# DAC.net
KiCad netlist of a schematic drawn in Altium Designer
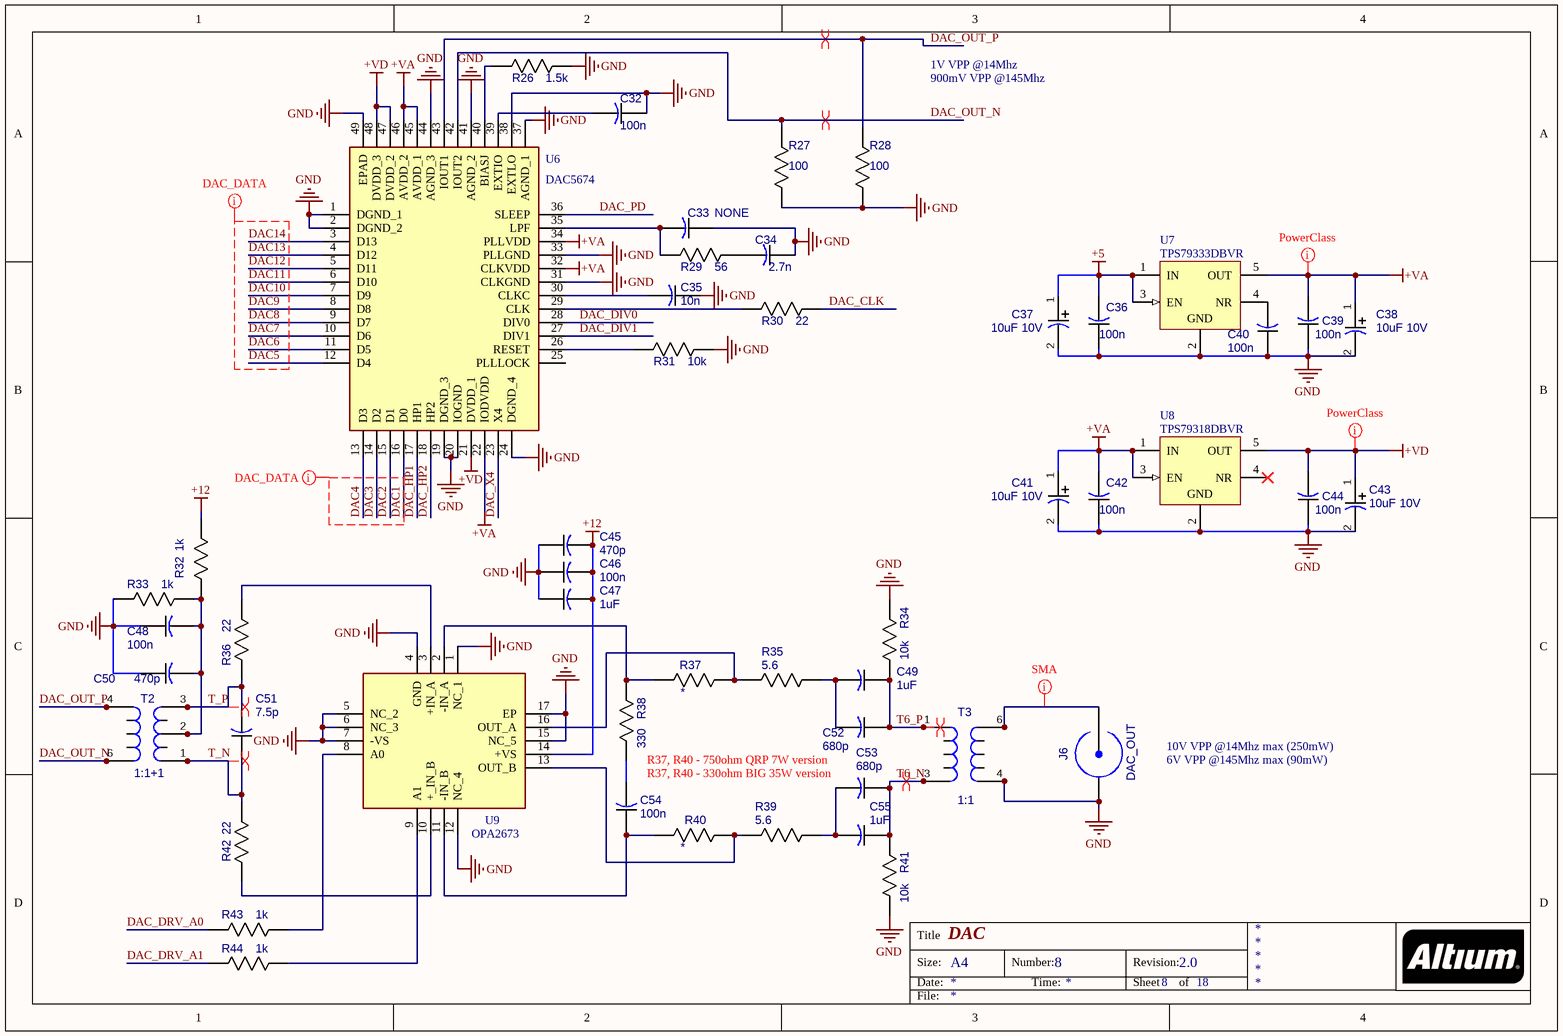
[diagram p0: DAC.SchDoc]

(export (version "E")
  (design (tool "Eeschema 10.0.6"))
  (components
    (comp (ref "C32")
      (value "100n")
      (footprint "CAP_0805")
      (description "CAP_0805")
      (libsource (lib "*") (part "CAP_0805"))
    )
    (comp (ref "C33")
      (value "NONE")
      (footprint "CAP_0805")
      (description "CAP_0805")
      (libsource (lib "*") (part "CAP_0805"))
    )
    (comp (ref "C34")
      (value "2.7n")
      (footprint "CAP_0805")
      (description "CAP_0805")
      (libsource (lib "*") (part "CAP_0805"))
    )
    (comp (ref "C35")
      (value "10n")
      (footprint "CAP_0805")
      (description "CAP_0805")
      (libsource (lib "*") (part "CAP_0805"))
    )
    (comp (ref "C36")
      (value "100n")
      (footprint "CAP_0805")
      (description "CAP_0805")
      (libsource (lib "*") (part "CAP_0805"))
    )
    (comp (ref "C37")
      (value "10uF 10V")
      (footprint "CAPAE_4.3x4.3h5.4")
      (description "CAPAE_4.3x4.3h5.4")
      (libsource (lib "MOTHERBOARD") (part "CAPAE_4.3x4.3h5.4"))
    )
    (comp (ref "C38")
      (value "10uF 10V")
      (footprint "CAPAE_4.3x4.3h5.4")
      (description "CAPAE_4.3x4.3h5.4")
      (libsource (lib "MOTHERBOARD") (part "CAPAE_4.3x4.3h5.4"))
    )
    (comp (ref "C39")
      (value "100n")
      (footprint "CAP_0805")
      (description "CAP_0805")
      (libsource (lib "*") (part "CAP_0805"))
    )
    (comp (ref "C40")
      (value "100n")
      (footprint "CAP_0805")
      (description "CAP_0805")
      (libsource (lib "*") (part "CAP_0805"))
    )
    (comp (ref "C41")
      (value "10uF 10V")
      (footprint "CAPAE_4.3x4.3h5.4")
      (description "CAPAE_4.3x4.3h5.4")
      (libsource (lib "MOTHERBOARD") (part "CAPAE_4.3x4.3h5.4"))
    )
    (comp (ref "C42")
      (value "100n")
      (footprint "CAP_0805")
      (description "CAP_0805")
      (libsource (lib "*") (part "CAP_0805"))
    )
    (comp (ref "C43")
      (value "10uF 10V")
      (footprint "CAPAE_4.3x4.3h5.4")
      (description "CAPAE_4.3x4.3h5.4")
      (libsource (lib "MOTHERBOARD") (part "CAPAE_4.3x4.3h5.4"))
    )
    (comp (ref "C44")
      (value "100n")
      (footprint "CAP_0805")
      (description "CAP_0805")
      (libsource (lib "*") (part "CAP_0805"))
    )
    (comp (ref "C45")
      (value "470p")
      (footprint "CAP_0805")
      (description "CAP_0805")
      (libsource (lib "*") (part "CAP_0805"))
    )
    (comp (ref "C46")
      (value "100n")
      (footprint "CAP_0805")
      (description "CAP_0805")
      (libsource (lib "*") (part "CAP_0805"))
    )
    (comp (ref "C47")
      (value "1uF")
      (footprint "CAP_0805")
      (description "CAP_0805")
      (libsource (lib "*") (part "CAP_0805"))
    )
    (comp (ref "C48")
      (value "100n")
      (footprint "CAP_0805")
      (description "CAP_0805")
      (libsource (lib "*") (part "CAP_0805"))
    )
    (comp (ref "C49")
      (value "1uF")
      (footprint "CAP_1206")
      (description "CAP_1206")
      (libsource (lib "*") (part "CAP_1206"))
    )
    (comp (ref "C50")
      (value "470p")
      (footprint "CAP_0805")
      (description "CAP_0805")
      (libsource (lib "*") (part "CAP_0805"))
    )
    (comp (ref "C51")
      (value "7.5p")
      (footprint "CAP_0805")
      (description "CAP_0805")
      (libsource (lib "*") (part "CAP_0805"))
    )
    (comp (ref "C52")
      (value "680p")
      (footprint "CAP_1206")
      (description "CAP_1206")
      (libsource (lib "*") (part "CAP_1206"))
    )
    (comp (ref "C53")
      (value "680p")
      (footprint "CAP_1206")
      (description "CAP_1206")
      (libsource (lib "*") (part "CAP_1206"))
    )
    (comp (ref "C54")
      (value "100n")
      (footprint "CAP_0805")
      (description "CAP_0805")
      (libsource (lib "*") (part "CAP_0805"))
    )
    (comp (ref "C55")
      (value "1uF")
      (footprint "CAP_1206")
      (description "CAP_1206")
      (libsource (lib "*") (part "CAP_1206"))
    )
    (comp (ref "J6")
      (value "DAC_OUT")
      (footprint "31-5431")
      (description "SMA")
      (libsource (lib "RF-UNIT_1") (part "31-5431"))
    )
    (comp (ref "R26")
      (value "1.5k")
      (footprint "RES_0805")
      (description "RES_0805")
      (libsource (lib "*") (part "RES_0805"))
    )
    (comp (ref "R27")
      (value "100")
      (footprint "RES_0805")
      (description "RES_0805")
      (libsource (lib "*") (part "RES_0805"))
    )
    (comp (ref "R28")
      (value "100")
      (footprint "RES_0805")
      (description "RES_0805")
      (libsource (lib "*") (part "RES_0805"))
    )
    (comp (ref "R29")
      (value "56")
      (footprint "RES_0805")
      (description "RES_0805")
      (libsource (lib "*") (part "RES_0805"))
    )
    (comp (ref "R30")
      (value "22")
      (footprint "RES_0805")
      (description "RES_0805")
      (libsource (lib "*") (part "RES_0805"))
    )
    (comp (ref "R31")
      (value "10k")
      (footprint "RES_0805")
      (description "RES_0805")
      (libsource (lib "*") (part "RES_0805"))
    )
    (comp (ref "R32")
      (value "1k")
      (footprint "RES_0805")
      (description "RES_0805")
      (libsource (lib "*") (part "RES_0805"))
    )
    (comp (ref "R33")
      (value "1k")
      (footprint "RES_0805")
      (description "RES_0805")
      (libsource (lib "*") (part "RES_0805"))
    )
    (comp (ref "R34")
      (value "10k")
      (footprint "RES_0805")
      (description "RES_0805")
      (libsource (lib "*") (part "RES_0805"))
    )
    (comp (ref "R35")
      (value "5.6")
      (footprint "RES_1206")
      (description "RES_1206")
      (libsource (lib "*") (part "RES_1206"))
    )
    (comp (ref "R36")
      (value "22")
      (footprint "RES_0805")
      (description "RES_0805")
      (libsource (lib "*") (part "RES_0805"))
    )
    (comp (ref "R37")
      (value "*")
      (footprint "RES_0805")
      (description "RES_0805")
      (libsource (lib "*") (part "RES_0805"))
    )
    (comp (ref "R38")
      (value "330")
      (footprint "RES_0805")
      (description "RES_0805")
      (libsource (lib "*") (part "RES_0805"))
    )
    (comp (ref "R39")
      (value "5.6")
      (footprint "RES_1206")
      (description "RES_1206")
      (libsource (lib "*") (part "RES_1206"))
    )
    (comp (ref "R40")
      (value "*")
      (footprint "RES_0805")
      (description "RES_0805")
      (libsource (lib "*") (part "RES_0805"))
    )
    (comp (ref "R41")
      (value "10k")
      (footprint "RES_0805")
      (description "RES_0805")
      (libsource (lib "*") (part "RES_0805"))
    )
    (comp (ref "R42")
      (value "22")
      (footprint "RES_0805")
      (description "RES_0805")
      (libsource (lib "*") (part "RES_0805"))
    )
    (comp (ref "R43")
      (value "1k")
      (footprint "RES_0805")
      (description "RES_0805")
      (libsource (lib "*") (part "RES_0805"))
    )
    (comp (ref "R44")
      (value "1k")
      (footprint "RES_0805")
      (description "RES_0805")
      (libsource (lib "*") (part "RES_0805"))
    )
    (comp (ref "T2")
      (value "1:1+1")
      (footprint "TRANSF_ACORE2")
      (description "Transformer")
      (libsource (lib "MOTHERBOARD_1") (part "TRANSF_ACORE2"))
    )
    (comp (ref "T3")
      (value "1:1")
      (footprint "TRANSF_ACORE")
      (description "Transformer")
      (libsource (lib "MOTHERBOARD_1") (part "TRANSF_ACORE"))
    )
    (comp (ref "U6")
      (value "DAC5674")
      (footprint "QFP50P900X900X100-49N")
      (description "Integrated Circuit")
      (fields (field (name "MANUFACTURER_PART_NUMBER") "DAC5674IPHP"))
      (libsource (lib "MOTHERBOARD") (part "DAC5674IPHP"))
    )
    (comp (ref "U7")
      (value "TPS79333DBVR")
      (footprint "DBV0005A_L")
      (fields (field (name "MANUFACTURER") "Texas Instruments"))
      (libsource (lib "Altium Content Vault") (part "TI-TPS79NXX-YYSOT5"))
    )
    (comp (ref "U8")
      (value "TPS79318DBVR")
      (footprint "DBV0005A_L")
      (fields (field (name "MANUFACTURER") "Texas Instruments"))
      (libsource (lib "Altium Content Vault") (part "TI-TPS79NXX-YYSOT5"))
    )
    (comp (ref "U9")
      (value "OPA2673")
      (footprint "QFN65P400X400X100-17N-D")
      (description "Integrated Circuit")
      (fields
        (field (name "MANUFACTURER_PART_NUMBER") "OPA2673IRGVT")
        (field (name "MOUSER PART NUMBER") "595-OPA2673IRGVT")
      )
      (libsource (lib "MOTHERBOARD") (part "OPA2673IRGVT"))
    )
  )
  (nets
    (net (code "1") (name "+5") (class "Default")
      (node (ref "C36") (pin "2") (pinfunction "2_2") (pintype "passive"))
      (node (ref "C37") (pin "1") (pinfunction "PLUS_1") (pintype "passive"))
      (node (ref "U7") (pin "1") (pinfunction "IN_1") (pintype "power_in"))
      (node (ref "U7") (pin "3") (pinfunction "EN_3") (pintype "input"))
    )
    (net (code "2") (name "+12") (class "Default")
      (node (ref "C45") (pin "2") (pinfunction "2_2") (pintype "passive"))
      (node (ref "C46") (pin "2") (pinfunction "2_2") (pintype "passive"))
      (node (ref "C47") (pin "2") (pinfunction "2_2") (pintype "passive"))
      (node (ref "R32") (pin "2") (pinfunction "2_2") (pintype "passive"))
      (node (ref "U9") (pin "14") (pinfunction "+VS_14") (pintype "passive"))
    )
    (net (code "3") (name "+VA") (class "Default")
      (node (ref "C38") (pin "1") (pinfunction "PLUS_1") (pintype "passive"))
      (node (ref "C39") (pin "2") (pinfunction "2_2") (pintype "passive"))
      (node (ref "C41") (pin "1") (pinfunction "PLUS_1") (pintype "passive"))
      (node (ref "C42") (pin "2") (pinfunction "2_2") (pintype "passive"))
      (node (ref "U6") (pin "22") (pinfunction "IODVDD_22") (pintype "passive"))
      (node (ref "U6") (pin "32") (pinfunction "CLKVDD_32") (pintype "passive"))
      (node (ref "U6") (pin "34") (pinfunction "PLLVDD_34") (pintype "passive"))
      (node (ref "U6") (pin "45") (pinfunction "AVDD_1_45") (pintype "passive"))
      (node (ref "U6") (pin "46") (pinfunction "AVDD_2_46") (pintype "passive"))
      (node (ref "U7") (pin "5") (pinfunction "OUT_5") (pintype "power_in"))
      (node (ref "U8") (pin "1") (pinfunction "IN_1") (pintype "power_in"))
      (node (ref "U8") (pin "3") (pinfunction "EN_3") (pintype "input"))
    )
    (net (code "4") (name "+VD") (class "Default")
      (node (ref "C43") (pin "1") (pinfunction "PLUS_1") (pintype "passive"))
      (node (ref "C44") (pin "2") (pinfunction "2_2") (pintype "passive"))
      (node (ref "U6") (pin "21") (pinfunction "DVDD_1_21") (pintype "passive"))
      (node (ref "U6") (pin "47") (pinfunction "DVDD_2_47") (pintype "passive"))
      (node (ref "U6") (pin "48") (pinfunction "DVDD_3_48") (pintype "passive"))
      (node (ref "U8") (pin "5") (pinfunction "OUT_5") (pintype "power_in"))
    )
    (net (code "5") (name "/DAC1") (class "Default")
      (node (ref "U6") (pin "16") (pinfunction "D0_16") (pintype "passive"))
    )
    (net (code "6") (name "/DAC2") (class "Default")
      (node (ref "U6") (pin "15") (pinfunction "D1_15") (pintype "passive"))
    )
    (net (code "7") (name "/DAC3") (class "Default")
      (node (ref "U6") (pin "14") (pinfunction "D2_14") (pintype "passive"))
    )
    (net (code "8") (name "/DAC4") (class "Default")
      (node (ref "U6") (pin "13") (pinfunction "D3_13") (pintype "passive"))
    )
    (net (code "9") (name "/DAC5") (class "Default")
      (node (ref "U6") (pin "12") (pinfunction "D4_12") (pintype "passive"))
    )
    (net (code "10") (name "/DAC6") (class "Default")
      (node (ref "U6") (pin "11") (pinfunction "D5_11") (pintype "passive"))
    )
    (net (code "11") (name "/DAC7") (class "Default")
      (node (ref "U6") (pin "10") (pinfunction "D6_10") (pintype "passive"))
    )
    (net (code "12") (name "/DAC8") (class "Default")
      (node (ref "U6") (pin "9") (pinfunction "D7_9") (pintype "passive"))
    )
    (net (code "13") (name "/DAC9") (class "Default")
      (node (ref "U6") (pin "8") (pinfunction "D8_8") (pintype "passive"))
    )
    (net (code "14") (name "/DAC10") (class "Default")
      (node (ref "U6") (pin "7") (pinfunction "D9_7") (pintype "passive"))
    )
    (net (code "15") (name "/DAC11") (class "Default")
      (node (ref "U6") (pin "6") (pinfunction "D10_6") (pintype "passive"))
    )
    (net (code "16") (name "/DAC12") (class "Default")
      (node (ref "U6") (pin "5") (pinfunction "D11_5") (pintype "passive"))
    )
    (net (code "17") (name "/DAC13") (class "Default")
      (node (ref "U6") (pin "4") (pinfunction "D12_4") (pintype "passive"))
    )
    (net (code "18") (name "/DAC14") (class "Default")
      (node (ref "U6") (pin "3") (pinfunction "D13_3") (pintype "passive"))
    )
    (net (code "19") (name "/DAC_CLK") (class "Default")
      (node (ref "R30") (pin "1") (pinfunction "1_1") (pintype "passive"))
    )
    (net (code "20") (name "/DAC_DIV0") (class "Default")
      (node (ref "U6") (pin "28") (pinfunction "DIV0_28") (pintype "passive"))
    )
    (net (code "21") (name "/DAC_DIV1") (class "Default")
      (node (ref "U6") (pin "27") (pinfunction "DIV1_27") (pintype "passive"))
    )
    (net (code "22") (name "/DAC_DRV_A0") (class "Default")
      (node (ref "R43") (pin "1") (pinfunction "1_1") (pintype "passive"))
    )
    (net (code "23") (name "/DAC_DRV_A1") (class "Default")
      (node (ref "R44") (pin "1") (pinfunction "1_1") (pintype "passive"))
    )
    (net (code "24") (name "/DAC_HP1") (class "Default")
      (node (ref "U6") (pin "17") (pinfunction "HP1_17") (pintype "passive"))
    )
    (net (code "25") (name "/DAC_HP2") (class "Default")
      (node (ref "U6") (pin "18") (pinfunction "HP2_18") (pintype "passive"))
    )
    (net (code "26") (name "/DAC_OUT_N") (class "Default")
      (node (ref "R27") (pin "2") (pinfunction "2_2") (pintype "passive"))
      (node (ref "T2") (pin "10") (pinfunction "0_10") (pintype "passive"))
      (node (ref "T2") (pin "6") (pinfunction "P2_6") (pintype "passive"))
      (node (ref "U6") (pin "42") (pinfunction "IOUT2_42") (pintype "passive"))
    )
    (net (code "27") (name "/DAC_OUT_P") (class "Default")
      (node (ref "R28") (pin "2") (pinfunction "2_2") (pintype "passive"))
      (node (ref "T2") (pin "11") (pinfunction "0_11") (pintype "passive"))
      (node (ref "T2") (pin "4") (pinfunction "P1_4") (pintype "passive"))
      (node (ref "U6") (pin "43") (pinfunction "IOUT1_43") (pintype "passive"))
    )
    (net (code "28") (name "/DAC_PD") (class "Default")
      (node (ref "U6") (pin "36") (pinfunction "SLEEP_36") (pintype "passive"))
    )
    (net (code "29") (name "/DAC_X4") (class "Default")
      (node (ref "U6") (pin "23") (pinfunction "X4_23") (pintype "passive"))
    )
    (net (code "30") (name "/T6_N") (class "Default")
      (node (ref "C53") (pin "1") (pinfunction "1_1") (pintype "passive"))
      (node (ref "C55") (pin "1") (pinfunction "1_1") (pintype "passive"))
      (node (ref "R41") (pin "1") (pinfunction "1_1") (pintype "passive"))
      (node (ref "T3") (pin "3") (pinfunction "P2_3") (pintype "passive"))
      (node (ref "T3") (pin "9") (pinfunction "0_9") (pintype "passive"))
    )
    (net (code "31") (name "/T6_P") (class "Default")
      (node (ref "C49") (pin "1") (pinfunction "1_1") (pintype "passive"))
      (node (ref "C52") (pin "1") (pinfunction "1_1") (pintype "passive"))
      (node (ref "R34") (pin "2") (pinfunction "2_2") (pintype "passive"))
      (node (ref "T3") (pin "1") (pinfunction "P1_1") (pintype "passive"))
      (node (ref "T3") (pin "7") (pinfunction "0_7") (pintype "passive"))
    )
    (net (code "32") (name "/T_N") (class "Default")
      (node (ref "C51") (pin "1") (pinfunction "1_1") (pintype "passive"))
      (node (ref "R42") (pin "2") (pinfunction "2_2") (pintype "passive"))
      (node (ref "T2") (pin "1") (pinfunction "S3_1") (pintype "passive"))
      (node (ref "T2") (pin "7") (pinfunction "0_7") (pintype "passive"))
    )
    (net (code "33") (name "/T_P") (class "Default")
      (node (ref "C51") (pin "2") (pinfunction "2_2") (pintype "passive"))
      (node (ref "R36") (pin "1") (pinfunction "1_1") (pintype "passive"))
      (node (ref "T2") (pin "3") (pinfunction "S1_3") (pintype "passive"))
      (node (ref "T2") (pin "9") (pinfunction "0_9") (pintype "passive"))
    )
    (net (code "34") (name "GND") (class "Default")
      (node (ref "C32") (pin "1") (pinfunction "1_1") (pintype "passive"))
      (node (ref "C33") (pin "1") (pinfunction "1_1") (pintype "passive"))
      (node (ref "C34") (pin "1") (pinfunction "1_1") (pintype "passive"))
      (node (ref "C35") (pin "1") (pinfunction "1_1") (pintype "passive"))
      (node (ref "C36") (pin "1") (pinfunction "1_1") (pintype "passive"))
      (node (ref "C37") (pin "2") (pinfunction "MINUS_2") (pintype "passive"))
      (node (ref "C38") (pin "2") (pinfunction "MINUS_2") (pintype "passive"))
      (node (ref "C39") (pin "1") (pinfunction "1_1") (pintype "passive"))
      (node (ref "C40") (pin "1") (pinfunction "1_1") (pintype "passive"))
      (node (ref "C41") (pin "2") (pinfunction "MINUS_2") (pintype "passive"))
      (node (ref "C42") (pin "1") (pinfunction "1_1") (pintype "passive"))
      (node (ref "C43") (pin "2") (pinfunction "MINUS_2") (pintype "passive"))
      (node (ref "C44") (pin "1") (pinfunction "1_1") (pintype "passive"))
      (node (ref "C45") (pin "1") (pinfunction "1_1") (pintype "passive"))
      (node (ref "C46") (pin "1") (pinfunction "1_1") (pintype "passive"))
      (node (ref "C47") (pin "1") (pinfunction "1_1") (pintype "passive"))
      (node (ref "C48") (pin "1") (pinfunction "1_1") (pintype "passive"))
      (node (ref "C50") (pin "1") (pinfunction "1_1") (pintype "passive"))
      (node (ref "J6") (pin "1") (pinfunction "GND_1") (pintype "passive"))
      (node (ref "J6") (pin "2") (pinfunction "GND_2") (pintype "passive"))
      (node (ref "J6") (pin "3") (pinfunction "GND_3") (pintype "passive"))
      (node (ref "J6") (pin "4") (pinfunction "GND_4") (pintype "passive"))
      (node (ref "R26") (pin "1") (pinfunction "1_1") (pintype "passive"))
      (node (ref "R27") (pin "1") (pinfunction "1_1") (pintype "passive"))
      (node (ref "R28") (pin "1") (pinfunction "1_1") (pintype "passive"))
      (node (ref "R31") (pin "1") (pinfunction "1_1") (pintype "passive"))
      (node (ref "R33") (pin "2") (pinfunction "2_2") (pintype "passive"))
      (node (ref "R34") (pin "1") (pinfunction "1_1") (pintype "passive"))
      (node (ref "R41") (pin "2") (pinfunction "2_2") (pintype "passive"))
      (node (ref "T3") (pin "11") (pinfunction "0_11") (pintype "passive"))
      (node (ref "T3") (pin "4") (pinfunction "S2_4") (pintype "passive"))
      (node (ref "U6") (pin "1") (pinfunction "DGND_1_1") (pintype "passive"))
      (node (ref "U6") (pin "19") (pinfunction "DGND_3_19") (pintype "passive"))
      (node (ref "U6") (pin "2") (pinfunction "DGND_2_2") (pintype "passive"))
      (node (ref "U6") (pin "20") (pinfunction "IOGND_20") (pintype "passive"))
      (node (ref "U6") (pin "24") (pinfunction "DGND_4_24") (pintype "passive"))
      (node (ref "U6") (pin "31") (pinfunction "CLKGND_31") (pintype "passive"))
      (node (ref "U6") (pin "33") (pinfunction "PLLGND_33") (pintype "passive"))
      (node (ref "U6") (pin "37") (pinfunction "AGND_1_37") (pintype "passive"))
      (node (ref "U6") (pin "38") (pinfunction "EXTLO_38") (pintype "passive"))
      (node (ref "U6") (pin "41") (pinfunction "AGND_2_41") (pintype "passive"))
      (node (ref "U6") (pin "44") (pinfunction "AGND_3_44") (pintype "passive"))
      (node (ref "U6") (pin "49") (pinfunction "EPAD_49") (pintype "passive"))
      (node (ref "U7") (pin "2") (pinfunction "GND_2") (pintype "power_in"))
      (node (ref "U8") (pin "2") (pinfunction "GND_2") (pintype "power_in"))
      (node (ref "U9") (pin "1") (pinfunction "NC_1_1") (pintype "passive"))
      (node (ref "U9") (pin "12") (pinfunction "NC_4_12") (pintype "passive"))
      (node (ref "U9") (pin "15") (pinfunction "NC_5_15") (pintype "passive"))
      (node (ref "U9") (pin "17") (pinfunction "EP_17") (pintype "passive"))
      (node (ref "U9") (pin "4") (pinfunction "GND_4") (pintype "passive"))
      (node (ref "U9") (pin "5") (pinfunction "NC_2_5") (pintype "passive"))
      (node (ref "U9") (pin "6") (pinfunction "NC_3_6") (pintype "passive"))
      (node (ref "U9") (pin "7") (pinfunction "-VS_7") (pintype "passive"))
    )
    (net (code "35") (name "Net-(C34-Pad2)") (class "Default")
      (node (ref "C34") (pin "2") (pinfunction "2_2") (pintype "passive"))
      (node (ref "R29") (pin "1") (pinfunction "1_1") (pintype "passive"))
    )
    (net (code "36") (name "Net-(C49-Pad2)") (class "Default")
      (node (ref "C49") (pin "2") (pinfunction "2_2") (pintype "passive"))
      (node (ref "C52") (pin "2") (pinfunction "2_2") (pintype "passive"))
      (node (ref "R35") (pin "1") (pinfunction "1_1") (pintype "passive"))
    )
    (net (code "37") (name "Net-(C53-Pad2)") (class "Default")
      (node (ref "C53") (pin "2") (pinfunction "2_2") (pintype "passive"))
      (node (ref "C55") (pin "2") (pinfunction "2_2") (pintype "passive"))
      (node (ref "R39") (pin "1") (pinfunction "1_1") (pintype "passive"))
    )
    (net (code "38") (name "Net-(C54-Pad2)") (class "Default")
      (node (ref "C54") (pin "2") (pinfunction "2_2") (pintype "passive"))
      (node (ref "R38") (pin "2") (pinfunction "2_2") (pintype "passive"))
    )
    (net (code "39") (name "Net-(J6-CON)") (class "Default")
      (node (ref "J6") (pin "5") (pinfunction "CON_5") (pintype "passive"))
      (node (ref "T3") (pin "10") (pinfunction "0_10") (pintype "passive"))
      (node (ref "T3") (pin "6") (pinfunction "S1_6") (pintype "passive"))
    )
    (net (code "40") (name "Net-(T2-S2)") (class "Default")
      (node (ref "C48") (pin "2") (pinfunction "2_2") (pintype "passive"))
      (node (ref "C50") (pin "2") (pinfunction "2_2") (pintype "passive"))
      (node (ref "R32") (pin "1") (pinfunction "1_1") (pintype "passive"))
      (node (ref "R33") (pin "1") (pinfunction "1_1") (pintype "passive"))
      (node (ref "T2") (pin "2") (pinfunction "S2_2") (pintype "passive"))
      (node (ref "T2") (pin "8") (pinfunction "0_8") (pintype "passive"))
    )
    (net (code "41") (name "Net-(U6-BIASJ)") (class "Default")
      (node (ref "R26") (pin "2") (pinfunction "2_2") (pintype "passive"))
      (node (ref "U6") (pin "40") (pinfunction "BIASJ_40") (pintype "passive"))
    )
    (net (code "42") (name "Net-(U6-CLK)") (class "Default")
      (node (ref "R30") (pin "2") (pinfunction "2_2") (pintype "passive"))
      (node (ref "U6") (pin "29") (pinfunction "CLK_29") (pintype "passive"))
    )
    (net (code "43") (name "Net-(U6-CLKC)") (class "Default")
      (node (ref "C35") (pin "2") (pinfunction "2_2") (pintype "passive"))
      (node (ref "U6") (pin "30") (pinfunction "CLKC_30") (pintype "passive"))
    )
    (net (code "44") (name "Net-(U6-EXTIO)") (class "Default")
      (node (ref "C32") (pin "2") (pinfunction "2_2") (pintype "passive"))
      (node (ref "U6") (pin "39") (pinfunction "EXTIO_39") (pintype "passive"))
    )
    (net (code "45") (name "Net-(U6-LPF)") (class "Default")
      (node (ref "C33") (pin "2") (pinfunction "2_2") (pintype "passive"))
      (node (ref "R29") (pin "2") (pinfunction "2_2") (pintype "passive"))
      (node (ref "U6") (pin "35") (pinfunction "LPF_35") (pintype "passive"))
    )
    (net (code "46") (name "Net-(U6-RESET)") (class "Default")
      (node (ref "R31") (pin "2") (pinfunction "2_2") (pintype "passive"))
      (node (ref "U6") (pin "26") (pinfunction "RESET_26") (pintype "passive"))
    )
    (net (code "47") (name "Net-(U7-NR)") (class "Default")
      (node (ref "C40") (pin "2") (pinfunction "2_2") (pintype "passive"))
      (node (ref "U7") (pin "4") (pinfunction "NR_4") (pintype "passive"))
    )
    (net (code "48") (name "Net-(U9-+IN_A)") (class "Default")
      (node (ref "R36") (pin "2") (pinfunction "2_2") (pintype "passive"))
      (node (ref "U9") (pin "3") (pinfunction "+IN_A_3") (pintype "passive"))
    )
    (net (code "49") (name "Net-(U9-+_IN_B)") (class "Default")
      (node (ref "R42") (pin "1") (pinfunction "1_1") (pintype "passive"))
      (node (ref "U9") (pin "10") (pinfunction "+_IN_B_10") (pintype "passive"))
    )
    (net (code "50") (name "Net-(U9--IN_A)") (class "Default")
      (node (ref "R37") (pin "2") (pinfunction "2_2") (pintype "passive"))
      (node (ref "R38") (pin "1") (pinfunction "1_1") (pintype "passive"))
      (node (ref "U9") (pin "2") (pinfunction "-IN_A_2") (pintype "passive"))
    )
    (net (code "51") (name "Net-(U9--IN_B)") (class "Default")
      (node (ref "C54") (pin "1") (pinfunction "1_1") (pintype "passive"))
      (node (ref "R40") (pin "2") (pinfunction "2_2") (pintype "passive"))
      (node (ref "U9") (pin "11") (pinfunction "-IN_B_11") (pintype "passive"))
    )
    (net (code "52") (name "Net-(U9-A0)") (class "Default")
      (node (ref "R43") (pin "2") (pinfunction "2_2") (pintype "passive"))
      (node (ref "U9") (pin "8") (pinfunction "A0_8") (pintype "passive"))
    )
    (net (code "53") (name "Net-(U9-A1)") (class "Default")
      (node (ref "R44") (pin "2") (pinfunction "2_2") (pintype "passive"))
      (node (ref "U9") (pin "9") (pinfunction "A1_9") (pintype "passive"))
    )
    (net (code "54") (name "Net-(U9-OUT_A)") (class "Default")
      (node (ref "R35") (pin "2") (pinfunction "2_2") (pintype "passive"))
      (node (ref "R37") (pin "1") (pinfunction "1_1") (pintype "passive"))
      (node (ref "U9") (pin "16") (pinfunction "OUT_A_16") (pintype "passive"))
    )
    (net (code "55") (name "Net-(U9-OUT_B)") (class "Default")
      (node (ref "R39") (pin "2") (pinfunction "2_2") (pintype "passive"))
      (node (ref "R40") (pin "1") (pinfunction "1_1") (pintype "passive"))
      (node (ref "U9") (pin "13") (pinfunction "OUT_B_13") (pintype "passive"))
    )
    (net (code "56") (name "unconnected-(T3-0-Pad8)") (class "Default")
      (node (ref "T3") (pin "8") (pinfunction "0_8") (pintype "passive"))
    )
    (net (code "57") (name "unconnected-(U6-PLLLOCK-Pad25)") (class "Default")
      (node (ref "U6") (pin "25") (pinfunction "PLLLOCK_25") (pintype "passive"))
    )
    (net (code "58") (name "unconnected-(U8-NR-Pad4)") (class "Default")
      (node (ref "U8") (pin "4") (pinfunction "NR_4") (pintype "passive+no_connect"))
    )
  )
)
